# BoB_Brain_v01.net
KiCad netlist of a schematic drawn in EAGLE
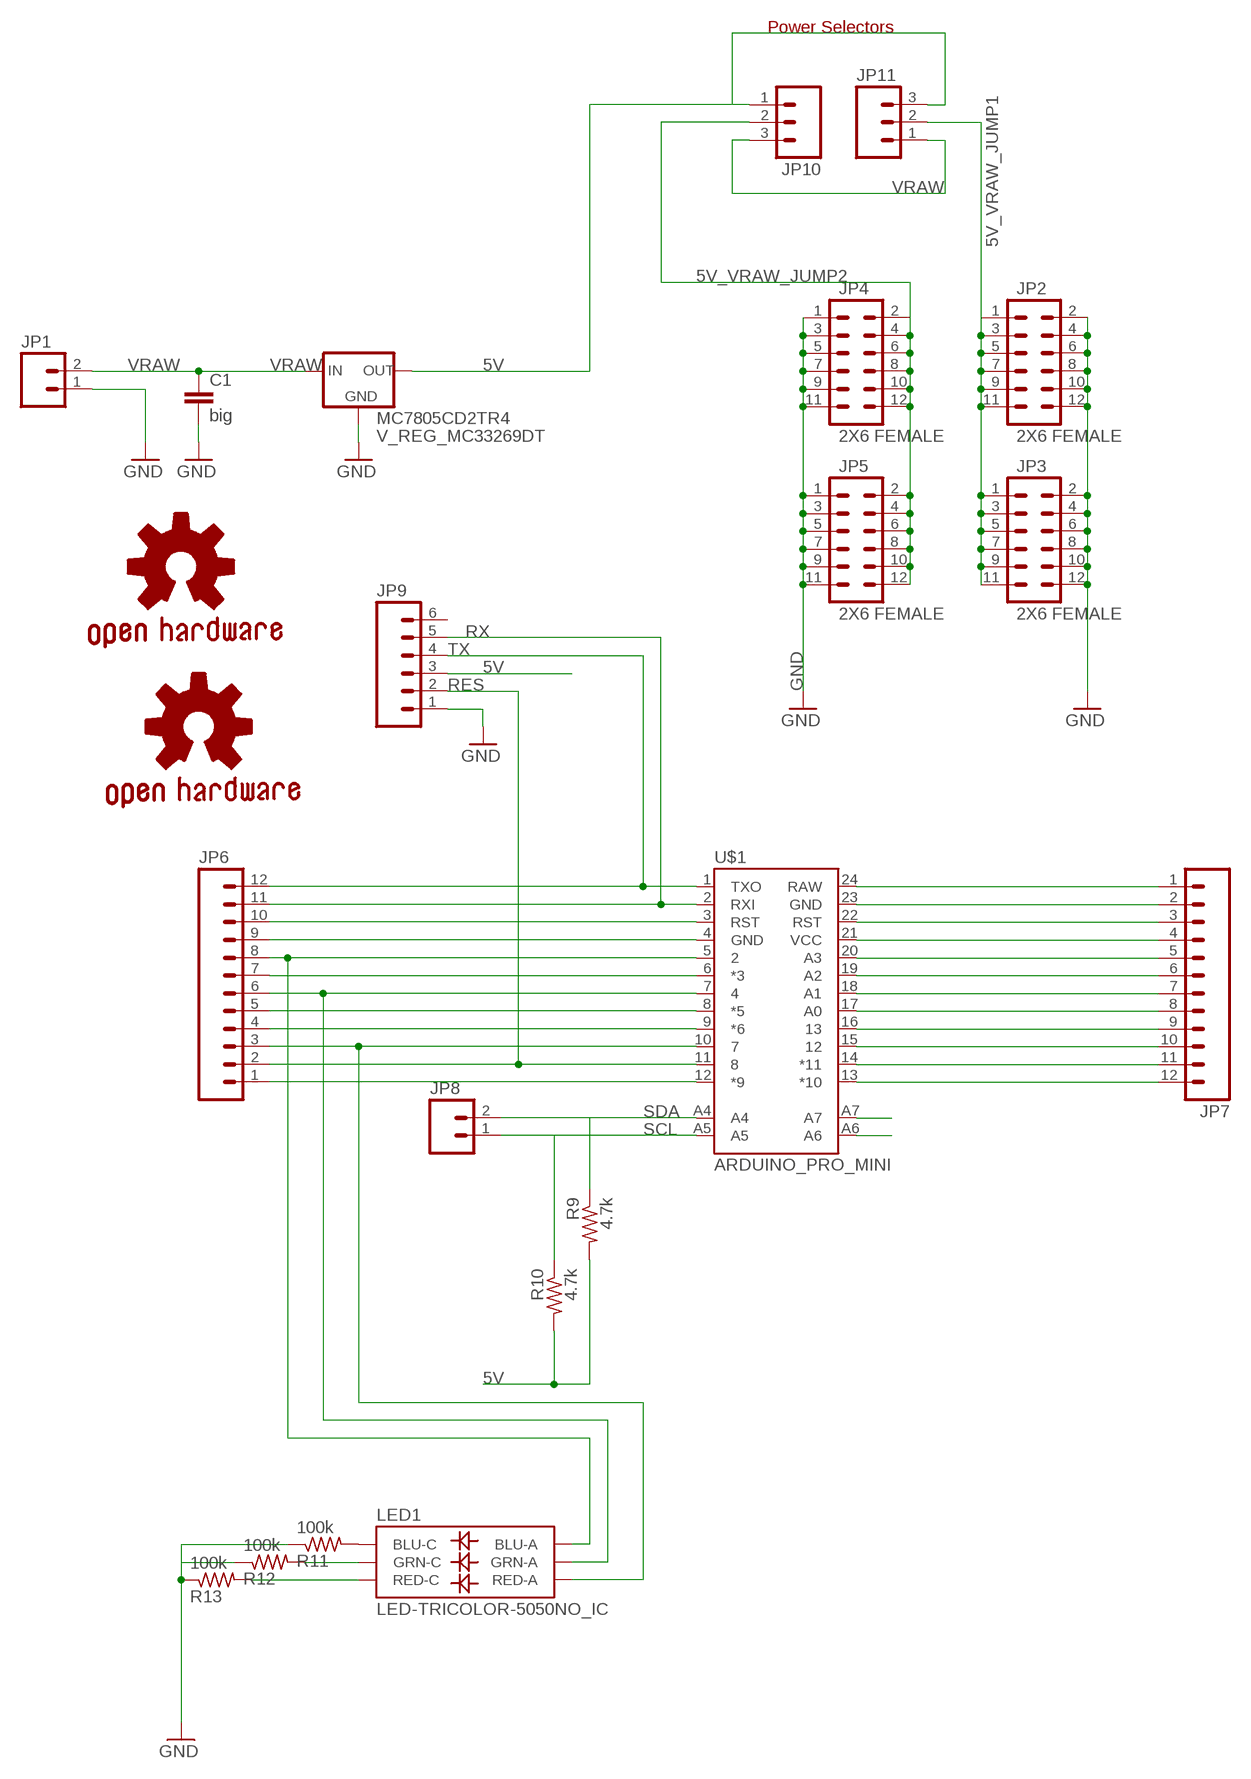
[diagram p0: schematic, sheet 1]

(export (version "E")
  (design (tool "Eeschema 10.0.6"))
  (components
    (comp (ref "C1")
      (value "big")
      (footprint "eagle-import:CAP-PTH-5MM")
      (libsource (lib "eagle-import") (part "CAPPTH1"))
    )
    (comp (ref "GOLD_ORB_SM1")
      (value "OSHWLOGO_GOLD_ORB_MED")
      (footprint "eagle-import:OSHW1")
      (libsource (lib "eagle-import") (part "OSHWLOGO_GOLD_ORB_MED"))
    )
    (comp (ref "GOLD_ORB_SM2")
      (value "OSHWLOGO_GOLD_ORB_SM")
      (footprint "eagle-import:OSHW2")
      (libsource (lib "eagle-import") (part "OSHWLOGO_GOLD_ORB_SM"))
    )
    (comp (ref "JP1")
      (value "M025MM")
      (footprint "eagle-import:SCREWTERMINAL-5MM-2")
      (libsource (lib "eagle-import") (part "M025MM"))
    )
    (comp (ref "JP2")
      (value "2X6 FEMALE")
      (footprint "eagle-import:2X6")
      (libsource (lib "eagle-import") (part "M06X2PTH_FEMALE"))
    )
    (comp (ref "JP3")
      (value "2X6 FEMALE")
      (footprint "eagle-import:2X6")
      (libsource (lib "eagle-import") (part "M06X2PTH_FEMALE"))
    )
    (comp (ref "JP4")
      (value "2X6 FEMALE")
      (footprint "eagle-import:2X6")
      (libsource (lib "eagle-import") (part "M06X2PTH_FEMALE"))
    )
    (comp (ref "JP5")
      (value "2X6 FEMALE")
      (footprint "eagle-import:2X6")
      (libsource (lib "eagle-import") (part "M06X2PTH_FEMALE"))
    )
    (comp (ref "JP6")
      (value "M12PTH")
      (footprint "eagle-import:1X12")
      (libsource (lib "eagle-import") (part "M12PTH"))
    )
    (comp (ref "JP7")
      (value "M12PTH")
      (footprint "eagle-import:1X12")
      (libsource (lib "eagle-import") (part "M12PTH"))
    )
    (comp (ref "JP8")
      (value "M02LOCK")
      (footprint "eagle-import:1X02_LOCK")
      (libsource (lib "eagle-import") (part "M02LOCK"))
    )
    (comp (ref "JP9")
      (value "M06LOCK")
      (footprint "eagle-import:1X06_LOCK")
      (libsource (lib "eagle-import") (part "M06LOCK"))
    )
    (comp (ref "JP10")
      (value "M03PTH")
      (footprint "eagle-import:1X03")
      (libsource (lib "eagle-import") (part "M03PTH"))
    )
    (comp (ref "JP11")
      (value "M03PTH")
      (footprint "eagle-import:1X03")
      (libsource (lib "eagle-import") (part "M03PTH"))
    )
    (comp (ref "LED1")
      (value "LED-TRICOLOR-5050NO_IC")
      (footprint "eagle-import:LED-TRICOLOR-5050")
      (libsource (lib "eagle-import") (part "LED-TRICOLOR-5050NO_IC"))
    )
    (comp (ref "MC7805CD2TR4")
      (value "V_REG_MC33269DT")
      (footprint "eagle-import:DPAK")
      (libsource (lib "eagle-import") (part "V_REG_MC33269DT"))
    )
    (comp (ref "R9")
      (value "4.7k")
      (footprint "eagle-import:M0805")
      (libsource (lib "eagle-import") (part "R-US_M0805"))
    )
    (comp (ref "R10")
      (value "4.7k")
      (footprint "eagle-import:M0805")
      (libsource (lib "eagle-import") (part "R-US_M0805"))
    )
    (comp (ref "R11")
      (value "100k")
      (footprint "eagle-import:R0805W")
      (libsource (lib "eagle-import") (part "R-US_R0805W"))
    )
    (comp (ref "R12")
      (value "100k")
      (footprint "eagle-import:R0805W")
      (libsource (lib "eagle-import") (part "R-US_R0805W"))
    )
    (comp (ref "R13")
      (value "100k")
      (footprint "eagle-import:R0805W")
      (libsource (lib "eagle-import") (part "R-US_R0805W"))
    )
    (comp (ref "U$1")
      (value "ARDUINO_PRO_MINI")
      (footprint "eagle-import:ARDUINO_PRO_MINI")
      (libsource (lib "eagle-import") (part "ARDUINO_PRO_MINI"))
    )
  )
  (nets
    (net (code "1") (name "/5V") (class "Default")
      (node (ref "JP10") (pin "1") (pinfunction "1_1") (pintype "passive"))
      (node (ref "JP11") (pin "3") (pinfunction "3_3") (pintype "passive"))
      (node (ref "JP9") (pin "3") (pinfunction "3_3") (pintype "passive"))
      (node (ref "MC7805CD2TR4") (pin "4") (pinfunction "OUT_4") (pintype "passive"))
      (node (ref "R10") (pin "2") (pinfunction "2_2") (pintype "passive"))
      (node (ref "R9") (pin "2") (pinfunction "2_2") (pintype "passive"))
    )
    (net (code "2") (name "/5V_VRAW_JUMP1") (class "Default")
      (node (ref "JP11") (pin "2") (pinfunction "2_2") (pintype "passive"))
      (node (ref "JP2") (pin "1") (pinfunction "1_1") (pintype "passive"))
      (node (ref "JP2") (pin "11") (pinfunction "11_11") (pintype "passive"))
      (node (ref "JP2") (pin "3") (pinfunction "3_3") (pintype "passive"))
      (node (ref "JP2") (pin "5") (pinfunction "5_5") (pintype "passive"))
      (node (ref "JP2") (pin "7") (pinfunction "7_7") (pintype "passive"))
      (node (ref "JP2") (pin "9") (pinfunction "9_9") (pintype "passive"))
      (node (ref "JP3") (pin "1") (pinfunction "1_1") (pintype "passive"))
      (node (ref "JP3") (pin "11") (pinfunction "11_11") (pintype "passive"))
      (node (ref "JP3") (pin "3") (pinfunction "3_3") (pintype "passive"))
      (node (ref "JP3") (pin "5") (pinfunction "5_5") (pintype "passive"))
      (node (ref "JP3") (pin "7") (pinfunction "7_7") (pintype "passive"))
      (node (ref "JP3") (pin "9") (pinfunction "9_9") (pintype "passive"))
    )
    (net (code "3") (name "/5V_VRAW_JUMP2") (class "Default")
      (node (ref "JP10") (pin "2") (pinfunction "2_2") (pintype "passive"))
      (node (ref "JP4") (pin "10") (pinfunction "10_10") (pintype "passive"))
      (node (ref "JP4") (pin "12") (pinfunction "12_12") (pintype "passive"))
      (node (ref "JP4") (pin "2") (pinfunction "2_2") (pintype "passive"))
      (node (ref "JP4") (pin "4") (pinfunction "4_4") (pintype "passive"))
      (node (ref "JP4") (pin "6") (pinfunction "6_6") (pintype "passive"))
      (node (ref "JP4") (pin "8") (pinfunction "8_8") (pintype "passive"))
      (node (ref "JP5") (pin "10") (pinfunction "10_10") (pintype "passive"))
      (node (ref "JP5") (pin "12") (pinfunction "12_12") (pintype "passive"))
      (node (ref "JP5") (pin "2") (pinfunction "2_2") (pintype "passive"))
      (node (ref "JP5") (pin "4") (pinfunction "4_4") (pintype "passive"))
      (node (ref "JP5") (pin "6") (pinfunction "6_6") (pintype "passive"))
      (node (ref "JP5") (pin "8") (pinfunction "8_8") (pintype "passive"))
    )
    (net (code "4") (name "/RES") (class "Default")
      (node (ref "JP6") (pin "2") (pinfunction "2_2") (pintype "passive"))
      (node (ref "JP9") (pin "2") (pinfunction "2_2") (pintype "passive"))
      (node (ref "U$1") (pin "11") (pinfunction "8_11") (pintype "bidirectional"))
    )
    (net (code "5") (name "/RX") (class "Default")
      (node (ref "JP6") (pin "11") (pinfunction "11_11") (pintype "passive"))
      (node (ref "JP9") (pin "5") (pinfunction "5_5") (pintype "passive"))
      (node (ref "U$1") (pin "2") (pinfunction "RXI_2") (pintype "bidirectional"))
    )
    (net (code "6") (name "/SCL") (class "Default")
      (node (ref "JP8") (pin "1") (pinfunction "1_1") (pintype "passive"))
      (node (ref "R10") (pin "1") (pinfunction "1_1") (pintype "passive"))
      (node (ref "U$1") (pin "A5") (pinfunction "A5_A5") (pintype "bidirectional"))
    )
    (net (code "7") (name "/SDA") (class "Default")
      (node (ref "JP8") (pin "2") (pinfunction "2_2") (pintype "passive"))
      (node (ref "R9") (pin "1") (pinfunction "1_1") (pintype "passive"))
      (node (ref "U$1") (pin "A4") (pinfunction "A4_A4") (pintype "bidirectional"))
    )
    (net (code "8") (name "/TX") (class "Default")
      (node (ref "JP6") (pin "12") (pinfunction "12_12") (pintype "passive"))
      (node (ref "JP9") (pin "4") (pinfunction "4_4") (pintype "passive"))
      (node (ref "U$1") (pin "1") (pinfunction "TXO_1") (pintype "bidirectional"))
    )
    (net (code "9") (name "/VRAW") (class "Default")
      (node (ref "C1") (pin "1") (pinfunction "1_1") (pintype "passive"))
      (node (ref "JP1") (pin "2") (pinfunction "2_2") (pintype "passive"))
      (node (ref "JP10") (pin "3") (pinfunction "3_3") (pintype "passive"))
      (node (ref "JP11") (pin "1") (pinfunction "1_1") (pintype "passive"))
      (node (ref "MC7805CD2TR4") (pin "3") (pinfunction "IN_3") (pintype "input"))
    )
    (net (code "10") (name "GND") (class "Default")
      (node (ref "C1") (pin "2") (pinfunction "2_2") (pintype "passive"))
      (node (ref "JP1") (pin "1") (pinfunction "1_1") (pintype "passive"))
      (node (ref "JP2") (pin "10") (pinfunction "10_10") (pintype "passive"))
      (node (ref "JP2") (pin "12") (pinfunction "12_12") (pintype "passive"))
      (node (ref "JP2") (pin "2") (pinfunction "2_2") (pintype "passive"))
      (node (ref "JP2") (pin "4") (pinfunction "4_4") (pintype "passive"))
      (node (ref "JP2") (pin "6") (pinfunction "6_6") (pintype "passive"))
      (node (ref "JP2") (pin "8") (pinfunction "8_8") (pintype "passive"))
      (node (ref "JP3") (pin "10") (pinfunction "10_10") (pintype "passive"))
      (node (ref "JP3") (pin "12") (pinfunction "12_12") (pintype "passive"))
      (node (ref "JP3") (pin "2") (pinfunction "2_2") (pintype "passive"))
      (node (ref "JP3") (pin "4") (pinfunction "4_4") (pintype "passive"))
      (node (ref "JP3") (pin "6") (pinfunction "6_6") (pintype "passive"))
      (node (ref "JP3") (pin "8") (pinfunction "8_8") (pintype "passive"))
      (node (ref "JP4") (pin "1") (pinfunction "1_1") (pintype "passive"))
      (node (ref "JP4") (pin "11") (pinfunction "11_11") (pintype "passive"))
      (node (ref "JP4") (pin "3") (pinfunction "3_3") (pintype "passive"))
      (node (ref "JP4") (pin "5") (pinfunction "5_5") (pintype "passive"))
      (node (ref "JP4") (pin "7") (pinfunction "7_7") (pintype "passive"))
      (node (ref "JP4") (pin "9") (pinfunction "9_9") (pintype "passive"))
      (node (ref "JP5") (pin "1") (pinfunction "1_1") (pintype "passive"))
      (node (ref "JP5") (pin "11") (pinfunction "11_11") (pintype "passive"))
      (node (ref "JP5") (pin "3") (pinfunction "3_3") (pintype "passive"))
      (node (ref "JP5") (pin "5") (pinfunction "5_5") (pintype "passive"))
      (node (ref "JP5") (pin "7") (pinfunction "7_7") (pintype "passive"))
      (node (ref "JP5") (pin "9") (pinfunction "9_9") (pintype "passive"))
      (node (ref "JP9") (pin "1") (pinfunction "1_1") (pintype "passive"))
      (node (ref "MC7805CD2TR4") (pin "1") (pinfunction "GND_1") (pintype "input"))
      (node (ref "R11") (pin "1") (pinfunction "1_1") (pintype "passive"))
      (node (ref "R12") (pin "1") (pinfunction "1_1") (pintype "passive"))
      (node (ref "R13") (pin "1") (pinfunction "1_1") (pintype "passive"))
    )
    (net (code "11") (name "Net-(JP6-Pad9)") (class "Default")
      (node (ref "JP6") (pin "9") (pinfunction "9_9") (pintype "passive"))
      (node (ref "U$1") (pin "4") (pinfunction "GND_4") (pintype "bidirectional"))
    )
    (net (code "12") (name "Net-(JP6-Pad10)") (class "Default")
      (node (ref "JP6") (pin "10") (pinfunction "10_10") (pintype "passive"))
      (node (ref "U$1") (pin "3") (pinfunction "RST_3") (pintype "bidirectional"))
    )
    (net (code "13") (name "Net-(JP7-Pad2)") (class "Default")
      (node (ref "JP7") (pin "2") (pinfunction "2_2") (pintype "passive"))
      (node (ref "U$1") (pin "23") (pinfunction "GND_23") (pintype "bidirectional"))
    )
    (net (code "14") (name "Net-(JP7-Pad3)") (class "Default")
      (node (ref "JP7") (pin "3") (pinfunction "3_3") (pintype "passive"))
      (node (ref "U$1") (pin "22") (pinfunction "RST_22") (pintype "bidirectional"))
    )
    (net (code "15") (name "Net-(LED1-BLU-A)") (class "Default")
      (node (ref "JP6") (pin "8") (pinfunction "8_8") (pintype "passive"))
      (node (ref "LED1") (pin "3") (pinfunction "BLU-A_3") (pintype "bidirectional"))
      (node (ref "U$1") (pin "5") (pinfunction "2_5") (pintype "bidirectional"))
    )
    (net (code "16") (name "Net-(LED1-BLU-C)") (class "Default")
      (node (ref "LED1") (pin "4") (pinfunction "BLU-C_4") (pintype "bidirectional"))
      (node (ref "R11") (pin "2") (pinfunction "2_2") (pintype "passive"))
    )
    (net (code "17") (name "Net-(LED1-GRN-A)") (class "Default")
      (node (ref "JP6") (pin "6") (pinfunction "6_6") (pintype "passive"))
      (node (ref "LED1") (pin "1") (pinfunction "GRN-A_1") (pintype "bidirectional"))
      (node (ref "U$1") (pin "7") (pinfunction "4_7") (pintype "bidirectional"))
    )
    (net (code "18") (name "Net-(LED1-GRN-C)") (class "Default")
      (node (ref "LED1") (pin "6") (pinfunction "GRN-C_6") (pintype "bidirectional"))
      (node (ref "R12") (pin "2") (pinfunction "2_2") (pintype "passive"))
    )
    (net (code "19") (name "Net-(LED1-RED-A)") (class "Default")
      (node (ref "JP6") (pin "3") (pinfunction "3_3") (pintype "passive"))
      (node (ref "LED1") (pin "2") (pinfunction "RED-A_2") (pintype "bidirectional"))
      (node (ref "U$1") (pin "10") (pinfunction "7_10") (pintype "bidirectional"))
    )
    (net (code "20") (name "Net-(LED1-RED-C)") (class "Default")
      (node (ref "LED1") (pin "5") (pinfunction "RED-C_5") (pintype "bidirectional"))
      (node (ref "R13") (pin "2") (pinfunction "2_2") (pintype "passive"))
    )
    (net (code "21") (name "Net-(U$1-*3)") (class "Default")
      (node (ref "JP6") (pin "7") (pinfunction "7_7") (pintype "passive"))
      (node (ref "U$1") (pin "6") (pinfunction "*3_6") (pintype "bidirectional"))
    )
    (net (code "22") (name "Net-(U$1-*5)") (class "Default")
      (node (ref "JP6") (pin "5") (pinfunction "5_5") (pintype "passive"))
      (node (ref "U$1") (pin "8") (pinfunction "*5_8") (pintype "bidirectional"))
    )
    (net (code "23") (name "Net-(U$1-*6)") (class "Default")
      (node (ref "JP6") (pin "4") (pinfunction "4_4") (pintype "passive"))
      (node (ref "U$1") (pin "9") (pinfunction "*6_9") (pintype "bidirectional"))
    )
    (net (code "24") (name "Net-(U$1-*9)") (class "Default")
      (node (ref "JP6") (pin "1") (pinfunction "1_1") (pintype "passive"))
      (node (ref "U$1") (pin "12") (pinfunction "*9_12") (pintype "bidirectional"))
    )
    (net (code "25") (name "Net-(U$1-*10)") (class "Default")
      (node (ref "JP7") (pin "12") (pinfunction "12_12") (pintype "passive"))
      (node (ref "U$1") (pin "13") (pinfunction "*10_13") (pintype "bidirectional"))
    )
    (net (code "26") (name "Net-(U$1-*11)") (class "Default")
      (node (ref "JP7") (pin "11") (pinfunction "11_11") (pintype "passive"))
      (node (ref "U$1") (pin "14") (pinfunction "*11_14") (pintype "bidirectional"))
    )
    (net (code "27") (name "Net-(U$1-12)") (class "Default")
      (node (ref "JP7") (pin "10") (pinfunction "10_10") (pintype "passive"))
      (node (ref "U$1") (pin "15") (pinfunction "12_15") (pintype "bidirectional"))
    )
    (net (code "28") (name "Net-(U$1-13)") (class "Default")
      (node (ref "JP7") (pin "9") (pinfunction "9_9") (pintype "passive"))
      (node (ref "U$1") (pin "16") (pinfunction "13_16") (pintype "bidirectional"))
    )
    (net (code "29") (name "Net-(U$1-A0)") (class "Default")
      (node (ref "JP7") (pin "8") (pinfunction "8_8") (pintype "passive"))
      (node (ref "U$1") (pin "17") (pinfunction "A0_17") (pintype "bidirectional"))
    )
    (net (code "30") (name "Net-(U$1-A1)") (class "Default")
      (node (ref "JP7") (pin "7") (pinfunction "7_7") (pintype "passive"))
      (node (ref "U$1") (pin "18") (pinfunction "A1_18") (pintype "bidirectional"))
    )
    (net (code "31") (name "Net-(U$1-A2)") (class "Default")
      (node (ref "JP7") (pin "6") (pinfunction "6_6") (pintype "passive"))
      (node (ref "U$1") (pin "19") (pinfunction "A2_19") (pintype "bidirectional"))
    )
    (net (code "32") (name "Net-(U$1-A3)") (class "Default")
      (node (ref "JP7") (pin "5") (pinfunction "5_5") (pintype "passive"))
      (node (ref "U$1") (pin "20") (pinfunction "A3_20") (pintype "bidirectional"))
    )
    (net (code "33") (name "Net-(U$1-RAW)") (class "Default")
      (node (ref "JP7") (pin "1") (pinfunction "1_1") (pintype "passive"))
      (node (ref "U$1") (pin "24") (pinfunction "RAW_24") (pintype "bidirectional"))
    )
    (net (code "34") (name "Net-(U$1-VCC)") (class "Default")
      (node (ref "JP7") (pin "4") (pinfunction "4_4") (pintype "passive"))
      (node (ref "U$1") (pin "21") (pinfunction "VCC_21") (pintype "bidirectional"))
    )
    (net (code "35") (name "unconnected-(JP9-Pad6)") (class "Default")
      (node (ref "JP9") (pin "6") (pinfunction "6_6") (pintype "passive"))
    )
    (net (code "36") (name "unconnected-(U$1-PadA6)") (class "Default")
      (node (ref "U$1") (pin "A6") (pinfunction "A6_A6") (pintype "bidirectional"))
    )
    (net (code "37") (name "unconnected-(U$1-PadA7)") (class "Default")
      (node (ref "U$1") (pin "A7") (pinfunction "A7_A7") (pintype "bidirectional"))
    )
  )
)
